# Output_Module.net
KiCad netlist of a schematic drawn in EAGLE
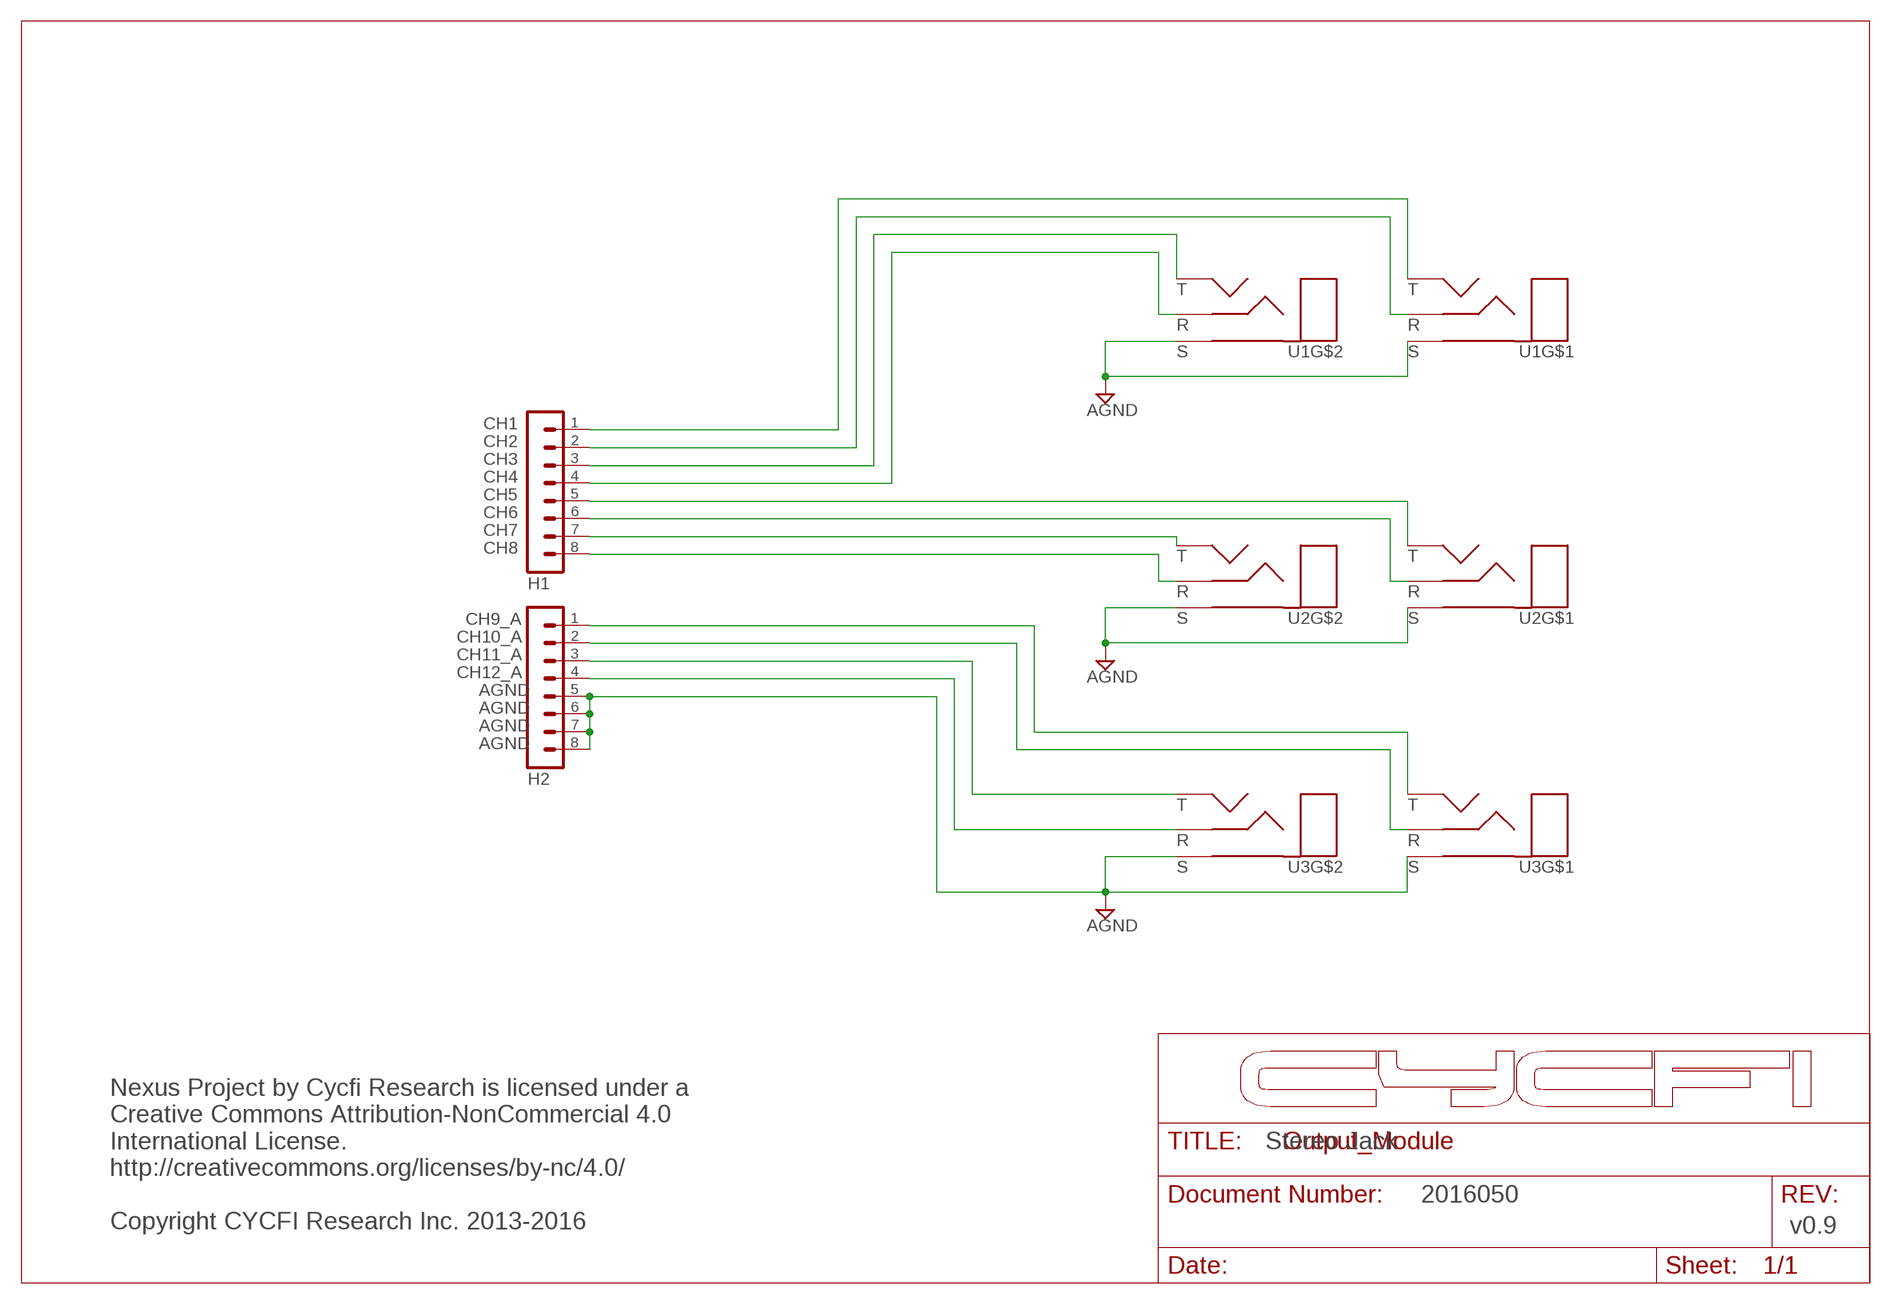
[diagram p0: schematic, sheet 1]

(export (version "E")
  (design (tool "Eeschema 10.0.6"))
  (components
    (comp (ref "H1")
      (value "MA08-1")
      (footprint "eagle-import:MA08-1")
      (libsource (lib "eagle-import") (part "MA08-1"))
    )
    (comp (ref "H2")
      (value "MA08-1")
      (footprint "eagle-import:MA08-1")
      (libsource (lib "eagle-import") (part "MA08-1"))
    )
    (comp (ref "U1")
      (value "AGND")
      (footprint "eagle-import:NSJ12HC")
      (libsource (lib "eagle-import") (part "NSJ12HC"))
    )
    (comp (ref "U2")
      (value "AGND")
      (footprint "eagle-import:NSJ12HC")
      (libsource (lib "eagle-import") (part "NSJ12HC"))
    )
    (comp (ref "U3")
      (value "AGND")
      (footprint "eagle-import:NSJ12HC")
      (libsource (lib "eagle-import") (part "NSJ12HC"))
    )
  )
  (nets
    (net (code "1") (name "/AGND") (class "Default")
      (node (ref "H2") (pin "5") (pinfunction "5_5") (pintype "passive"))
      (node (ref "H2") (pin "6") (pinfunction "6_6") (pintype "passive"))
      (node (ref "H2") (pin "7") (pinfunction "7_7") (pintype "passive"))
      (node (ref "H2") (pin "8") (pinfunction "8_8") (pintype "passive"))
      (node (ref "U1") (pin "G") (pinfunction "DGND_G") (pintype "power_in"))
      (node (ref "U1") (pin "SB") (pinfunction "S_SB") (pintype "bidirectional"))
      (node (ref "U1") (pin "ST") (pinfunction "S_ST") (pintype "bidirectional"))
      (node (ref "U2") (pin "G") (pinfunction "DGND_G") (pintype "power_in"))
      (node (ref "U2") (pin "SB") (pinfunction "S_SB") (pintype "bidirectional"))
      (node (ref "U2") (pin "ST") (pinfunction "S_ST") (pintype "bidirectional"))
      (node (ref "U3") (pin "G") (pinfunction "DGND_G") (pintype "power_in"))
      (node (ref "U3") (pin "SB") (pinfunction "S_SB") (pintype "bidirectional"))
      (node (ref "U3") (pin "ST") (pinfunction "S_ST") (pintype "bidirectional"))
    )
    (net (code "2") (name "Net-(U1A-R)") (class "Default")
      (node (ref "H1") (pin "2") (pinfunction "2_2") (pintype "passive"))
      (node (ref "U1") (pin "RT") (pinfunction "R_RT") (pintype "bidirectional"))
    )
    (net (code "3") (name "Net-(U1A-T)") (class "Default")
      (node (ref "H1") (pin "1") (pinfunction "1_1") (pintype "passive"))
      (node (ref "U1") (pin "TT") (pinfunction "T_TT") (pintype "bidirectional"))
    )
    (net (code "4") (name "Net-(U1B-R)") (class "Default")
      (node (ref "H1") (pin "4") (pinfunction "4_4") (pintype "passive"))
      (node (ref "U1") (pin "RB") (pinfunction "R_RB") (pintype "bidirectional"))
    )
    (net (code "5") (name "Net-(U1B-T)") (class "Default")
      (node (ref "H1") (pin "3") (pinfunction "3_3") (pintype "passive"))
      (node (ref "U1") (pin "TB") (pinfunction "T_TB") (pintype "bidirectional"))
    )
    (net (code "6") (name "Net-(U2A-R)") (class "Default")
      (node (ref "H1") (pin "6") (pinfunction "6_6") (pintype "passive"))
      (node (ref "U2") (pin "RT") (pinfunction "R_RT") (pintype "bidirectional"))
    )
    (net (code "7") (name "Net-(U2A-T)") (class "Default")
      (node (ref "H1") (pin "5") (pinfunction "5_5") (pintype "passive"))
      (node (ref "U2") (pin "TT") (pinfunction "T_TT") (pintype "bidirectional"))
    )
    (net (code "8") (name "Net-(U2B-R)") (class "Default")
      (node (ref "H1") (pin "8") (pinfunction "8_8") (pintype "passive"))
      (node (ref "U2") (pin "RB") (pinfunction "R_RB") (pintype "bidirectional"))
    )
    (net (code "9") (name "Net-(U2B-T)") (class "Default")
      (node (ref "H1") (pin "7") (pinfunction "7_7") (pintype "passive"))
      (node (ref "U2") (pin "TB") (pinfunction "T_TB") (pintype "bidirectional"))
    )
    (net (code "10") (name "Net-(U3A-R)") (class "Default")
      (node (ref "H2") (pin "2") (pinfunction "2_2") (pintype "passive"))
      (node (ref "U3") (pin "RT") (pinfunction "R_RT") (pintype "bidirectional"))
    )
    (net (code "11") (name "Net-(U3A-T)") (class "Default")
      (node (ref "H2") (pin "1") (pinfunction "1_1") (pintype "passive"))
      (node (ref "U3") (pin "TT") (pinfunction "T_TT") (pintype "bidirectional"))
    )
    (net (code "12") (name "Net-(U3B-R)") (class "Default")
      (node (ref "H2") (pin "4") (pinfunction "4_4") (pintype "passive"))
      (node (ref "U3") (pin "RB") (pinfunction "R_RB") (pintype "bidirectional"))
    )
    (net (code "13") (name "Net-(U3B-T)") (class "Default")
      (node (ref "H2") (pin "3") (pinfunction "3_3") (pintype "passive"))
      (node (ref "U3") (pin "TB") (pinfunction "T_TB") (pintype "bidirectional"))
    )
  )
)
